# ILI9341-Touch-connector.net
KiCad netlist of a schematic drawn in EAGLE
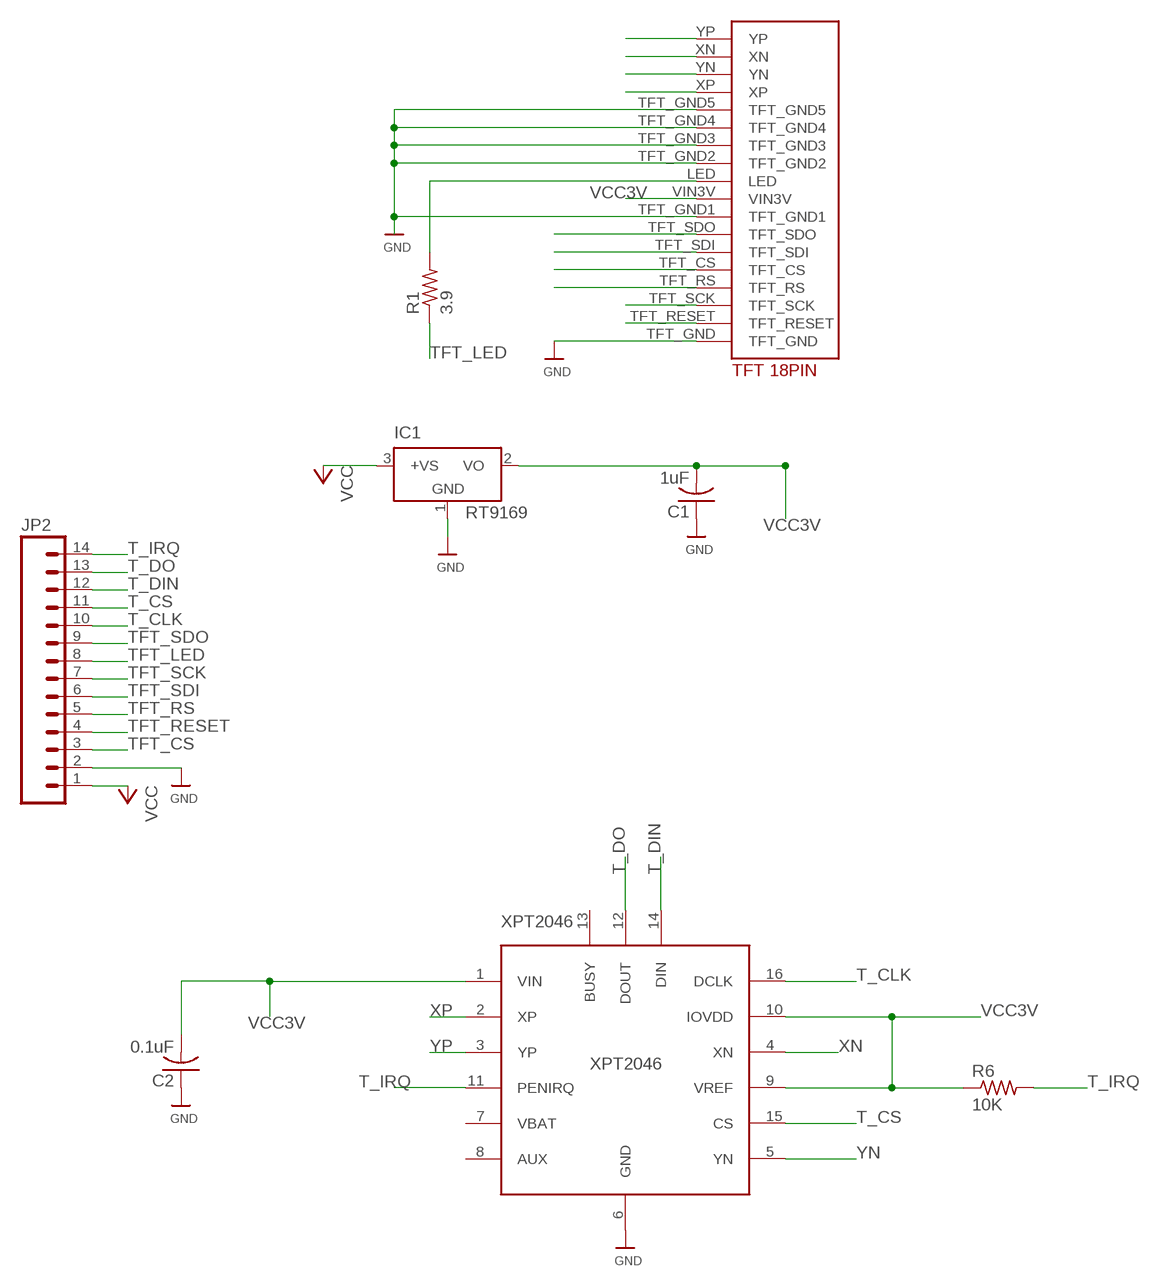
[diagram p0: schematic, sheet 1]

(export (version "E")
  (design (tool "Eeschema 10.0.6"))
  (components
    (comp (ref "C1")
      (value "1uF")
      (footprint "eagle-import:C0805K")
      (libsource (lib "eagle-import") (part "C-USC0805K"))
    )
    (comp (ref "C2")
      (value "0.1uF")
      (footprint "eagle-import:C0805K")
      (libsource (lib "eagle-import") (part "C-USC0805K"))
    )
    (comp (ref "IC1")
      (value "RT9169")
      (footprint "eagle-import:SOT23")
      (libsource (lib "eagle-import") (part "RT9169"))
    )
    (comp (ref "JP2")
      (value "M14")
      (footprint "eagle-import:1X14")
      (libsource (lib "eagle-import") (part "M14"))
    )
    (comp (ref "R1")
      (value "3.9")
      (footprint "eagle-import:R0805")
      (libsource (lib "eagle-import") (part "R-US_R0805"))
    )
    (comp (ref "R6")
      (value "10K")
      (footprint "eagle-import:R0805")
      (libsource (lib "eagle-import") (part "R-US_R0805"))
    )
    (comp (ref "U$4")
      (value "TFT_18PIN")
      (footprint "eagle-import:TFT_18PIN")
      (libsource (lib "eagle-import") (part "TFT_18PIN"))
    )
    (comp (ref "XPT2046")
      (value "XPT2046")
      (footprint "eagle-import:TSSOP16-EXPOSED_PAD_MINIMAL")
      (libsource (lib "eagle-import") (part "XPT2046TSSOP16-EXPOSED-PAD-MINIMAL"))
    )
  )
  (nets
    (net (code "1") (name "/TFT_CS") (class "Default")
      (node (ref "JP2") (pin "3") (pinfunction "3_3") (pintype "passive"))
      (node (ref "U$4") (pin "TFT_CS") (pinfunction "TFT_CS_TFT_CS") (pintype "bidirectional"))
    )
    (net (code "2") (name "/TFT_LED") (class "Default")
      (node (ref "JP2") (pin "8") (pinfunction "8_8") (pintype "passive"))
      (node (ref "R1") (pin "1") (pinfunction "1_1") (pintype "passive"))
    )
    (net (code "3") (name "/TFT_RESET") (class "Default")
      (node (ref "JP2") (pin "4") (pinfunction "4_4") (pintype "passive"))
      (node (ref "U$4") (pin "TFT_RESET") (pinfunction "TFT_RESET_TFT_RESET") (pintype "bidirectional"))
    )
    (net (code "4") (name "/TFT_RS") (class "Default")
      (node (ref "JP2") (pin "5") (pinfunction "5_5") (pintype "passive"))
      (node (ref "U$4") (pin "TFT_RS") (pinfunction "TFT_RS_TFT_RS") (pintype "bidirectional"))
    )
    (net (code "5") (name "/TFT_SCK") (class "Default")
      (node (ref "JP2") (pin "7") (pinfunction "7_7") (pintype "passive"))
      (node (ref "U$4") (pin "TFT_SCK") (pinfunction "TFT_SCK_TFT_SCK") (pintype "bidirectional"))
    )
    (net (code "6") (name "/TFT_SDI") (class "Default")
      (node (ref "JP2") (pin "6") (pinfunction "6_6") (pintype "passive"))
      (node (ref "U$4") (pin "TFT_SDI") (pinfunction "TFT_SDI_TFT_SDI") (pintype "bidirectional"))
    )
    (net (code "7") (name "/TFT_SDO") (class "Default")
      (node (ref "JP2") (pin "9") (pinfunction "9_9") (pintype "passive"))
      (node (ref "U$4") (pin "TFT_SDO") (pinfunction "TFT_SDO_TFT_SDO") (pintype "bidirectional"))
    )
    (net (code "8") (name "/T_CLK") (class "Default")
      (node (ref "JP2") (pin "10") (pinfunction "10_10") (pintype "passive"))
      (node (ref "XPT2046") (pin "16") (pinfunction "DCLK_16") (pintype "bidirectional"))
    )
    (net (code "9") (name "/T_CS") (class "Default")
      (node (ref "JP2") (pin "11") (pinfunction "11_11") (pintype "passive"))
      (node (ref "XPT2046") (pin "15") (pinfunction "CS_15") (pintype "bidirectional"))
    )
    (net (code "10") (name "/T_DIN") (class "Default")
      (node (ref "JP2") (pin "12") (pinfunction "12_12") (pintype "passive"))
      (node (ref "XPT2046") (pin "14") (pinfunction "DIN_14") (pintype "bidirectional"))
    )
    (net (code "11") (name "/T_DO") (class "Default")
      (node (ref "JP2") (pin "13") (pinfunction "13_13") (pintype "passive"))
      (node (ref "XPT2046") (pin "12") (pinfunction "DOUT_12") (pintype "bidirectional"))
    )
    (net (code "12") (name "/T_IRQ") (class "Default")
      (node (ref "JP2") (pin "14") (pinfunction "14_14") (pintype "passive"))
      (node (ref "R6") (pin "2") (pinfunction "2_2") (pintype "passive"))
      (node (ref "XPT2046") (pin "11") (pinfunction "PENIRQ_11") (pintype "bidirectional"))
    )
    (net (code "13") (name "/VCC3V") (class "Default")
      (node (ref "C1") (pin "2") (pinfunction "2_2") (pintype "passive"))
      (node (ref "C2") (pin "2") (pinfunction "2_2") (pintype "passive"))
      (node (ref "IC1") (pin "2") (pinfunction "VO_2") (pintype "input"))
      (node (ref "R6") (pin "1") (pinfunction "1_1") (pintype "passive"))
      (node (ref "U$4") (pin "VIN3V") (pinfunction "VIN3V_VIN3V") (pintype "bidirectional"))
      (node (ref "XPT2046") (pin "1") (pinfunction "VIN_1") (pintype "bidirectional"))
      (node (ref "XPT2046") (pin "10") (pinfunction "IOVDD_10") (pintype "bidirectional"))
      (node (ref "XPT2046") (pin "9") (pinfunction "VREF_9") (pintype "bidirectional"))
    )
    (net (code "14") (name "/XN") (class "Default")
      (node (ref "U$4") (pin "XN") (pinfunction "XN_XN") (pintype "bidirectional"))
      (node (ref "XPT2046") (pin "4") (pinfunction "XN_4") (pintype "bidirectional"))
    )
    (net (code "15") (name "/XP") (class "Default")
      (node (ref "U$4") (pin "XP") (pinfunction "XP_XP") (pintype "bidirectional"))
      (node (ref "XPT2046") (pin "2") (pinfunction "XP_2") (pintype "bidirectional"))
    )
    (net (code "16") (name "/YN") (class "Default")
      (node (ref "U$4") (pin "YN") (pinfunction "YN_YN") (pintype "bidirectional"))
      (node (ref "XPT2046") (pin "5") (pinfunction "YN_5") (pintype "bidirectional"))
    )
    (net (code "17") (name "/YP") (class "Default")
      (node (ref "U$4") (pin "YP") (pinfunction "YP_YP") (pintype "bidirectional"))
      (node (ref "XPT2046") (pin "3") (pinfunction "YP_3") (pintype "bidirectional"))
    )
    (net (code "18") (name "GND") (class "Default")
      (node (ref "C1") (pin "1") (pinfunction "1_1") (pintype "passive"))
      (node (ref "C2") (pin "1") (pinfunction "1_1") (pintype "passive"))
      (node (ref "IC1") (pin "1") (pinfunction "GND_1") (pintype "power_in"))
      (node (ref "JP2") (pin "2") (pinfunction "2_2") (pintype "passive"))
      (node (ref "U$4") (pin "TFT_GND") (pinfunction "TFT_GND_TFT_GND") (pintype "bidirectional"))
      (node (ref "U$4") (pin "TFT_GND1") (pinfunction "TFT_GND1_TFT_GND1") (pintype "bidirectional"))
      (node (ref "U$4") (pin "TFT_GND2") (pinfunction "TFT_GND2_TFT_GND2") (pintype "bidirectional"))
      (node (ref "U$4") (pin "TFT_GND3") (pinfunction "TFT_GND3_TFT_GND3") (pintype "bidirectional"))
      (node (ref "U$4") (pin "TFT_GND4") (pinfunction "TFT_GND4_TFT_GND4") (pintype "bidirectional"))
      (node (ref "U$4") (pin "TFT_GND5") (pinfunction "TFT_GND5_TFT_GND5") (pintype "bidirectional"))
      (node (ref "XPT2046") (pin "6") (pinfunction "GND_6") (pintype "bidirectional"))
    )
    (net (code "19") (name "Net-(R1-Pad2)") (class "Default")
      (node (ref "R1") (pin "2") (pinfunction "2_2") (pintype "passive"))
      (node (ref "U$4") (pin "LED") (pinfunction "LED_LED") (pintype "bidirectional"))
    )
    (net (code "20") (name "VCC") (class "Default")
      (node (ref "IC1") (pin "3") (pinfunction "+VS_3") (pintype "input"))
      (node (ref "JP2") (pin "1") (pinfunction "1_1") (pintype "passive"))
    )
    (net (code "21") (name "unconnected-(XPT2046-AUX-Pad8)") (class "Default")
      (node (ref "XPT2046") (pin "8") (pinfunction "AUX_8") (pintype "bidirectional"))
    )
    (net (code "22") (name "unconnected-(XPT2046-BUSY-Pad13)") (class "Default")
      (node (ref "XPT2046") (pin "13") (pinfunction "BUSY_13") (pintype "bidirectional"))
    )
    (net (code "23") (name "unconnected-(XPT2046-VBAT-Pad7)") (class "Default")
      (node (ref "XPT2046") (pin "7") (pinfunction "VBAT_7") (pintype "bidirectional"))
    )
  )
)
